# Sheet1.net
KiCad netlist of a schematic drawn in Altium Designer
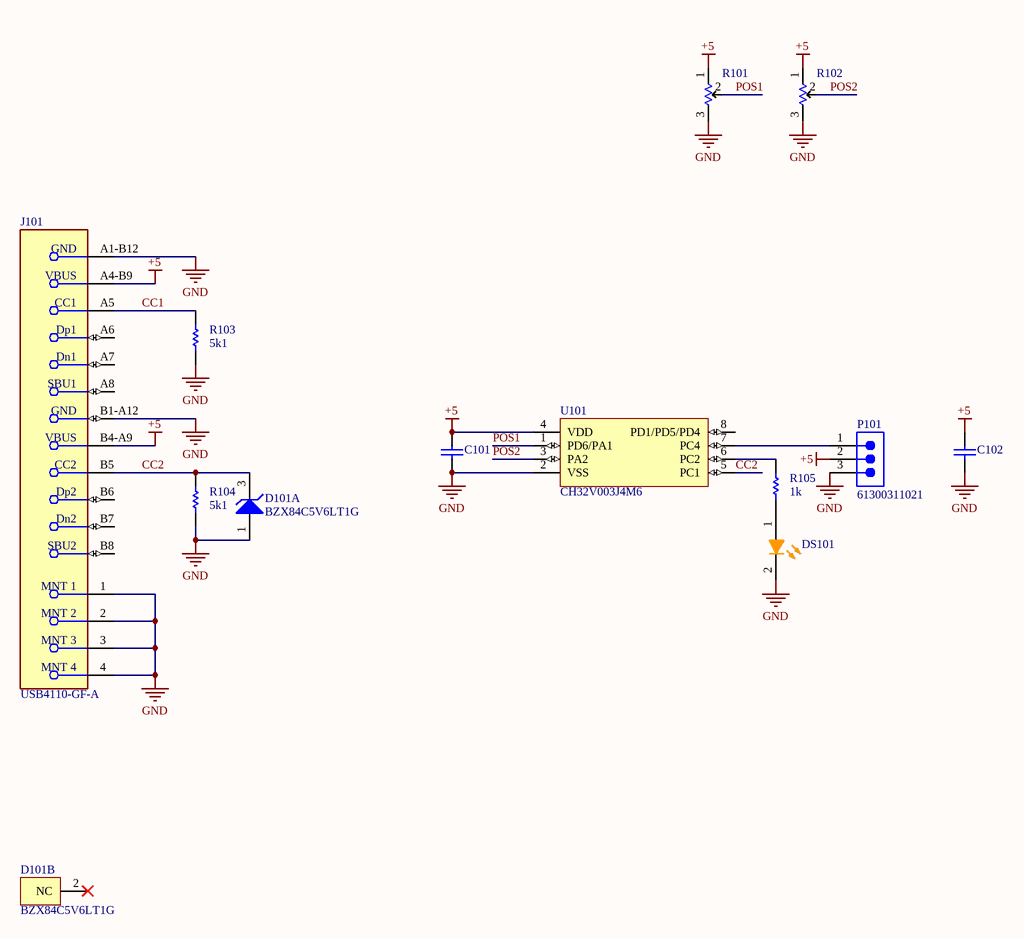
[diagram p0: Sheet1.SchDoc]

(export (version "E")
  (design (tool "Eeschema 10.0.6"))
  (components
    (comp (ref "C101")
      (value "Capacitor")
      (footprint "CAPC1608X09N")
      (libsource (lib "Schlib1") (part "C0603"))
    )
    (comp (ref "C102")
      (value "Capacitor")
      (footprint "CAPC1608X09N")
      (libsource (lib "Schlib1") (part "C0603"))
    )
    (comp (ref "D101")
      (value "BZX84C5V6LT1G")
      (footprint "ONSC-SOT-23-3-318-08_V")
      (description "Zener Voltage Regulator, 225 mW, 3-Pin SOT-23, Pb-Free, Tape and Reel")
      (fields (field (name "MANUFACTURER") "On Semiconductor"))
      (libsource (lib "Altium Content Vault") (part "ONSC-A1K3-3"))
    )
    (comp (ref "DS101")
      (value "KP-1608SECK")
      (footprint "KING-0603LED_ORANGE_V")
      (description "LED, SMT, 0603(1608), 1.1mm thickness, Orange")
      (fields (field (name "MANUFACTURER") "Kingbright"))
      (libsource (lib "Schlib1") (part "LED Orange"))
    )
    (comp (ref "J101")
      (value "USB4110-GF-A")
      (footprint "FP-USB4110-GF-A-MFG")
      (description "CONN USB 2.0 TYPE-C R/A SMT")
      (fields
        (field (name "OCTOPART") "https://octopart.com/usb4110-gf-a-gct-103941985")
        (field (name "MANUFACTURER") "GCT")
      )
      (libsource (lib "Altium Content Vault") (part "e23f2b38bb3c3f98e683ebab9ede730"))
    )
    (comp (ref "P101")
      (value "61300311021")
      (footprint "61300311021")
      (description "THT Angled Pin Header WR-PHD, Pitch 2.54 mm, Single Row, 3 pins")
      (libsource (lib "Altium Content Vault") (part "Header_Male_1R_03P"))
    )
    (comp (ref "R101")
      (value "Cermet Trimmer")
      (footprint "CERMET_TRIMMER_SMD")
      (description "SMD Trimmer Resistor")
      (fields (field (name "MANUFACTURER") "Bourns") (field (name "TOLERANCE") "5%"))
      (libsource (lib "Schlib1") (part "Trimmer_SMD"))
    )
    (comp (ref "R102")
      (value "Cermet Trimmer")
      (footprint "CERMET_TRIMMER_SMD")
      (description "SMD Trimmer Resistor")
      (fields (field (name "MANUFACTURER") "Bourns") (field (name "TOLERANCE") "5%"))
      (libsource (lib "Schlib1") (part "Trimmer_SMD"))
    )
    (comp (ref "R103")
      (value "5k1")
      (footprint "RESC1608X06N")
      (description "Resistor")
      (libsource (lib "Schlib1") (part "R0603"))
    )
    (comp (ref "R104")
      (value "5k1")
      (footprint "RESC1608X06N")
      (description "Resistor")
      (libsource (lib "Schlib1") (part "R0603"))
    )
    (comp (ref "R105")
      (value "1k")
      (footprint "RESC1608X06N")
      (description "Resistor")
      (libsource (lib "Schlib1") (part "R0603"))
    )
    (comp (ref "U101")
      (value "CH32V003J4M6")
      (footprint "SOIC127P600X155-8N")
      (libsource (lib "Schlib1") (part "CH32V003J4M6"))
    )
  )
  (nets
    (net (code "1") (name "+5") (class "Default")
      (node (ref "C101") (pin "2") (pintype "passive"))
      (node (ref "C102") (pin "2") (pintype "passive"))
      (node (ref "J101") (pin "A4-B9") (pinfunction "VBUS_A4-B9") (pintype "power_in"))
      (node (ref "J101") (pin "B4-A9") (pinfunction "VBUS_B4-A9") (pintype "power_in"))
      (node (ref "P101") (pin "2") (pinfunction "2_2") (pintype "passive"))
      (node (ref "R101") (pin "1") (pinfunction "CCW_1") (pintype "passive"))
      (node (ref "R102") (pin "1") (pinfunction "CCW_1") (pintype "passive"))
      (node (ref "U101") (pin "4") (pinfunction "VDD_4") (pintype "power_in"))
    )
    (net (code "2") (name "/CC1") (class "Default")
      (node (ref "J101") (pin "A5") (pinfunction "CC1_A5") (pintype "power_in"))
      (node (ref "R103") (pin "2") (pintype "passive"))
    )
    (net (code "3") (name "/CC2") (class "Default")
      (node (ref "D101") (pin "3") (pinfunction "K_3") (pintype "passive"))
      (node (ref "J101") (pin "B5") (pinfunction "CC2_B5") (pintype "power_in"))
      (node (ref "R104") (pin "2") (pintype "passive"))
      (node (ref "U101") (pin "5") (pinfunction "PC1_5") (pintype "bidirectional"))
    )
    (net (code "4") (name "/POS1") (class "Default")
      (node (ref "R101") (pin "2") (pinfunction "WIPER_2") (pintype "passive"))
      (node (ref "U101") (pin "1") (pinfunction "PD6/PA1_1") (pintype "bidirectional"))
    )
    (net (code "5") (name "/POS2") (class "Default")
      (node (ref "R102") (pin "2") (pinfunction "WIPER_2") (pintype "passive"))
      (node (ref "U101") (pin "3") (pinfunction "PA2_3") (pintype "bidirectional"))
    )
    (net (code "6") (name "GND") (class "Default")
      (node (ref "C101") (pin "1") (pintype "passive"))
      (node (ref "C102") (pin "1") (pintype "passive"))
      (node (ref "D101") (pin "1") (pinfunction "A_1") (pintype "passive"))
      (node (ref "DS101") (pin "2") (pinfunction "K_2") (pintype "passive"))
      (node (ref "J101") (pin "1") (pinfunction "MNT_1_1") (pintype "passive"))
      (node (ref "J101") (pin "2") (pinfunction "MNT_2_2") (pintype "passive"))
      (node (ref "J101") (pin "3") (pinfunction "MNT_3_3") (pintype "passive"))
      (node (ref "J101") (pin "4") (pinfunction "MNT_4_4") (pintype "passive"))
      (node (ref "J101") (pin "A1-B12") (pinfunction "GND_A1-B12") (pintype "passive"))
      (node (ref "J101") (pin "B1-A12") (pinfunction "GND_B1-A12") (pintype "bidirectional"))
      (node (ref "P101") (pin "3") (pinfunction "3_3") (pintype "passive"))
      (node (ref "R101") (pin "3") (pinfunction "CW_3") (pintype "passive"))
      (node (ref "R102") (pin "3") (pinfunction "CW_3") (pintype "passive"))
      (node (ref "R103") (pin "1") (pintype "passive"))
      (node (ref "R104") (pin "1") (pintype "passive"))
      (node (ref "U101") (pin "2") (pinfunction "VSS_2") (pintype "power_in"))
    )
    (net (code "7") (name "Net-(DS101-A)") (class "Default")
      (node (ref "DS101") (pin "1") (pinfunction "A_1") (pintype "passive"))
      (node (ref "R105") (pin "1") (pintype "passive"))
    )
    (net (code "8") (name "Net-(U101-PC2)") (class "Default")
      (node (ref "R105") (pin "2") (pintype "passive"))
      (node (ref "U101") (pin "6") (pinfunction "PC2_6") (pintype "bidirectional"))
    )
    (net (code "9") (name "Net-(U101-PC4)") (class "Default")
      (node (ref "P101") (pin "1") (pinfunction "1_1") (pintype "passive"))
      (node (ref "U101") (pin "7") (pinfunction "PC4_7") (pintype "bidirectional"))
    )
    (net (code "10") (name "unconnected-(D101B-NC-Pad2)") (class "Default")
      (node (ref "D101") (pin "2") (pinfunction "NC_2") (pintype "passive+no_connect"))
    )
    (net (code "11") (name "unconnected-(J101-Dn1-PadA7)") (class "Default")
      (node (ref "J101") (pin "A7") (pinfunction "Dn1_A7") (pintype "bidirectional"))
    )
    (net (code "12") (name "unconnected-(J101-Dn2-PadB7)") (class "Default")
      (node (ref "J101") (pin "B7") (pinfunction "Dn2_B7") (pintype "bidirectional"))
    )
    (net (code "13") (name "unconnected-(J101-Dp1-PadA6)") (class "Default")
      (node (ref "J101") (pin "A6") (pinfunction "Dp1_A6") (pintype "bidirectional"))
    )
    (net (code "14") (name "unconnected-(J101-Dp2-PadB6)") (class "Default")
      (node (ref "J101") (pin "B6") (pinfunction "Dp2_B6") (pintype "bidirectional"))
    )
    (net (code "15") (name "unconnected-(J101-SBU1-PadA8)") (class "Default")
      (node (ref "J101") (pin "A8") (pinfunction "SBU1_A8") (pintype "bidirectional"))
    )
    (net (code "16") (name "unconnected-(J101-SBU2-PadB8)") (class "Default")
      (node (ref "J101") (pin "B8") (pinfunction "SBU2_B8") (pintype "bidirectional"))
    )
    (net (code "17") (name "unconnected-(U101-PD1{slash}PD5{slash}PD4-Pad8)") (class "Default")
      (node (ref "U101") (pin "8") (pinfunction "PD1/PD5/PD4_8") (pintype "bidirectional"))
    )
  )
)
